# M18_36_Potis_V13.net
KiCad netlist of a schematic drawn in EAGLE
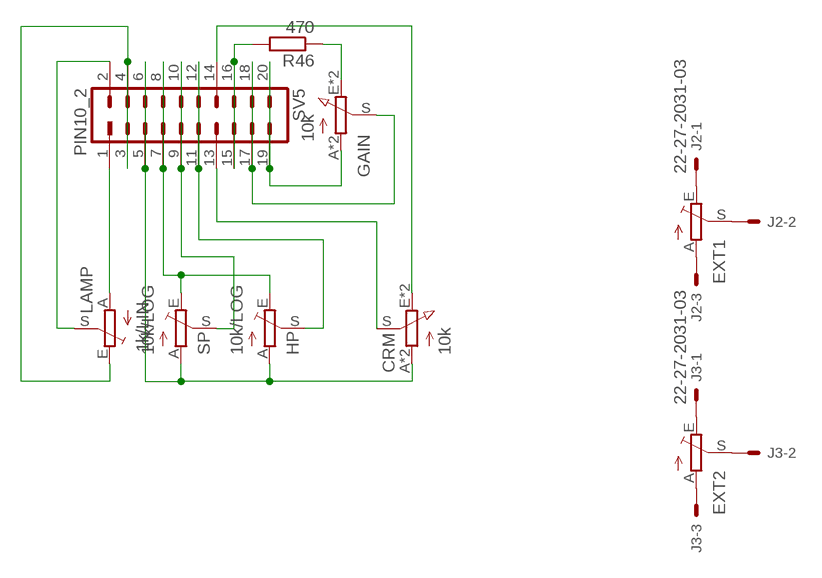
[diagram p0: schematic, sheet 1]

(export (version "E")
  (design (tool "Eeschema 10.0.6"))
  (components
    (comp (ref "CRM")
      (value "10k")
      (footprint "eagle-import:P_PT-10+15_KIEMELT_SZELES")
      (libsource (lib "eagle-import") (part "P_EUPT10+15_K_SZ"))
    )
    (comp (ref "EXT1")
      (value "TRIM_EU-PT10")
      (footprint "eagle-import:PT-10")
      (libsource (lib "eagle-import") (part "TRIM_EU-PT10"))
    )
    (comp (ref "EXT2")
      (value "TRIM_EU-PT10")
      (footprint "eagle-import:PT-10")
      (libsource (lib "eagle-import") (part "TRIM_EU-PT10"))
    )
    (comp (ref "GAIN")
      (value "10k")
      (footprint "eagle-import:P_PT-10+15_KIEMELT_SZELES")
      (libsource (lib "eagle-import") (part "P_EUPT10+15_K_SZ"))
    )
    (comp (ref "HP")
      (value "10k/LOG")
      (footprint "eagle-import:POT_NAR")
      (libsource (lib "eagle-import") (part "TRIM_EU-POT_WHOLE"))
    )
    (comp (ref "J2")
      (value "22-27-2031-03")
      (footprint "eagle-import:6410-03")
      (libsource (lib "eagle-import") (part "22-?-0327-2031"))
    )
    (comp (ref "J3")
      (value "22-27-2031-03")
      (footprint "eagle-import:6410-03")
      (libsource (lib "eagle-import") (part "22-?-0327-2031"))
    )
    (comp (ref "LAMP")
      (value "1k/LIN")
      (footprint "eagle-import:POT_NAR")
      (libsource (lib "eagle-import") (part "TRIM_EU-POT_WHOLE"))
    )
    (comp (ref "R46")
      (value "470")
      (footprint "eagle-import:R0805")
      (libsource (lib "eagle-import") (part "R-EU_R0805"))
    )
    (comp (ref "SP")
      (value "10k/LOG")
      (footprint "eagle-import:POT_NAR")
      (libsource (lib "eagle-import") (part "TRIM_EU-POT_WHOLE"))
    )
    (comp (ref "SV5")
      (value "PIN10_2")
      (footprint "eagle-import:PIN10_2")
      (libsource (lib "eagle-import") (part "PIN10_2"))
    )
  )
  (nets
    (net (code "1") (name "Net-(CRM-A-PadA1)") (class "Default")
      (node (ref "CRM") (pin "A") (pinfunction "A_A") (pintype "passive"))
      (node (ref "CRM") (pin "A1") (pinfunction "A_A1") (pintype "passive"))
      (node (ref "HP") (pin "A") (pinfunction "A_A") (pintype "passive"))
      (node (ref "SP") (pin "A") (pinfunction "A_A") (pintype "passive"))
      (node (ref "SV5") (pin "5") (pinfunction "5_5") (pintype "passive"))
      (node (ref "SV5") (pin "6") (pinfunction "6_6") (pintype "passive"))
    )
    (net (code "2") (name "Net-(CRM-E-PadE1)") (class "Default")
      (node (ref "CRM") (pin "E") (pinfunction "E_E") (pintype "passive"))
      (node (ref "CRM") (pin "E1") (pinfunction "E_E1") (pintype "passive"))
      (node (ref "SV5") (pin "14") (pinfunction "14_14") (pintype "passive"))
    )
    (net (code "3") (name "Net-(CRM-PadS)") (class "Default")
      (node (ref "CRM") (pin "S") (pinfunction "S_S") (pintype "passive"))
      (node (ref "SV5") (pin "13") (pinfunction "13_13") (pintype "passive"))
    )
    (net (code "4") (name "Net-(GAIN-A-PadA1)") (class "Default")
      (node (ref "GAIN") (pin "A") (pinfunction "A_A") (pintype "passive"))
      (node (ref "GAIN") (pin "A1") (pinfunction "A_A1") (pintype "passive"))
      (node (ref "SV5") (pin "19") (pinfunction "19_19") (pintype "passive"))
      (node (ref "SV5") (pin "20") (pinfunction "20_20") (pintype "passive"))
    )
    (net (code "5") (name "Net-(GAIN-E-PadE1)") (class "Default")
      (node (ref "GAIN") (pin "E") (pinfunction "E_E") (pintype "passive"))
      (node (ref "GAIN") (pin "E1") (pinfunction "E_E1") (pintype "passive"))
      (node (ref "R46") (pin "1") (pinfunction "1_1") (pintype "passive"))
    )
    (net (code "6") (name "Net-(GAIN-PadS)") (class "Default")
      (node (ref "GAIN") (pin "S") (pinfunction "S_S") (pintype "passive"))
      (node (ref "SV5") (pin "17") (pinfunction "17_17") (pintype "passive"))
      (node (ref "SV5") (pin "18") (pinfunction "18_18") (pintype "passive"))
    )
    (net (code "7") (name "Net-(HP-PadE)") (class "Default")
      (node (ref "HP") (pin "E") (pinfunction "E_E") (pintype "passive"))
      (node (ref "SP") (pin "E") (pinfunction "E_E") (pintype "passive"))
      (node (ref "SV5") (pin "7") (pinfunction "7_7") (pintype "passive"))
      (node (ref "SV5") (pin "8") (pinfunction "8_8") (pintype "passive"))
    )
    (net (code "8") (name "Net-(HP-PadS)") (class "Default")
      (node (ref "HP") (pin "S") (pinfunction "S_S") (pintype "passive"))
      (node (ref "SV5") (pin "11") (pinfunction "11_11") (pintype "passive"))
      (node (ref "SV5") (pin "12") (pinfunction "12_12") (pintype "passive"))
    )
    (net (code "9") (name "Net-(J2A-S)") (class "Default")
      (node (ref "EXT1") (pin "E") (pinfunction "E_E") (pintype "passive"))
      (node (ref "J2") (pin "1") (pinfunction "S_1") (pintype "passive"))
    )
    (net (code "10") (name "Net-(J2B-S)") (class "Default")
      (node (ref "EXT1") (pin "S") (pinfunction "S_S") (pintype "passive"))
      (node (ref "J2") (pin "2") (pinfunction "S_2") (pintype "passive"))
    )
    (net (code "11") (name "Net-(J2C-S)") (class "Default")
      (node (ref "EXT1") (pin "A") (pinfunction "A_A") (pintype "passive"))
      (node (ref "J2") (pin "3") (pinfunction "S_3") (pintype "passive"))
    )
    (net (code "12") (name "Net-(J3A-S)") (class "Default")
      (node (ref "EXT2") (pin "E") (pinfunction "E_E") (pintype "passive"))
      (node (ref "J3") (pin "1") (pinfunction "S_1") (pintype "passive"))
    )
    (net (code "13") (name "Net-(J3B-S)") (class "Default")
      (node (ref "EXT2") (pin "S") (pinfunction "S_S") (pintype "passive"))
      (node (ref "J3") (pin "2") (pinfunction "S_2") (pintype "passive"))
    )
    (net (code "14") (name "Net-(J3C-S)") (class "Default")
      (node (ref "EXT2") (pin "A") (pinfunction "A_A") (pintype "passive"))
      (node (ref "J3") (pin "3") (pinfunction "S_3") (pintype "passive"))
    )
    (net (code "15") (name "Net-(LAMP-PadA)") (class "Default")
      (node (ref "LAMP") (pin "A") (pinfunction "A_A") (pintype "passive"))
      (node (ref "SV5") (pin "1") (pinfunction "1_1") (pintype "passive"))
    )
    (net (code "16") (name "Net-(LAMP-PadE)") (class "Default")
      (node (ref "LAMP") (pin "E") (pinfunction "E_E") (pintype "passive"))
      (node (ref "SV5") (pin "3") (pinfunction "3_3") (pintype "passive"))
      (node (ref "SV5") (pin "4") (pinfunction "4_4") (pintype "passive"))
    )
    (net (code "17") (name "Net-(LAMP-PadS)") (class "Default")
      (node (ref "LAMP") (pin "S") (pinfunction "S_S") (pintype "passive"))
      (node (ref "SV5") (pin "2") (pinfunction "2_2") (pintype "passive"))
    )
    (net (code "18") (name "Net-(R46-Pad2)") (class "Default")
      (node (ref "R46") (pin "2") (pinfunction "2_2") (pintype "passive"))
      (node (ref "SV5") (pin "15") (pinfunction "15_15") (pintype "passive"))
      (node (ref "SV5") (pin "16") (pinfunction "16_16") (pintype "passive"))
    )
    (net (code "19") (name "Net-(SP-PadS)") (class "Default")
      (node (ref "SP") (pin "S") (pinfunction "S_S") (pintype "passive"))
      (node (ref "SV5") (pin "10") (pinfunction "10_10") (pintype "passive"))
      (node (ref "SV5") (pin "9") (pinfunction "9_9") (pintype "passive"))
    )
  )
)
